# pulzn_regul_tor.net
KiCad netlist of a schematic drawn in EAGLE
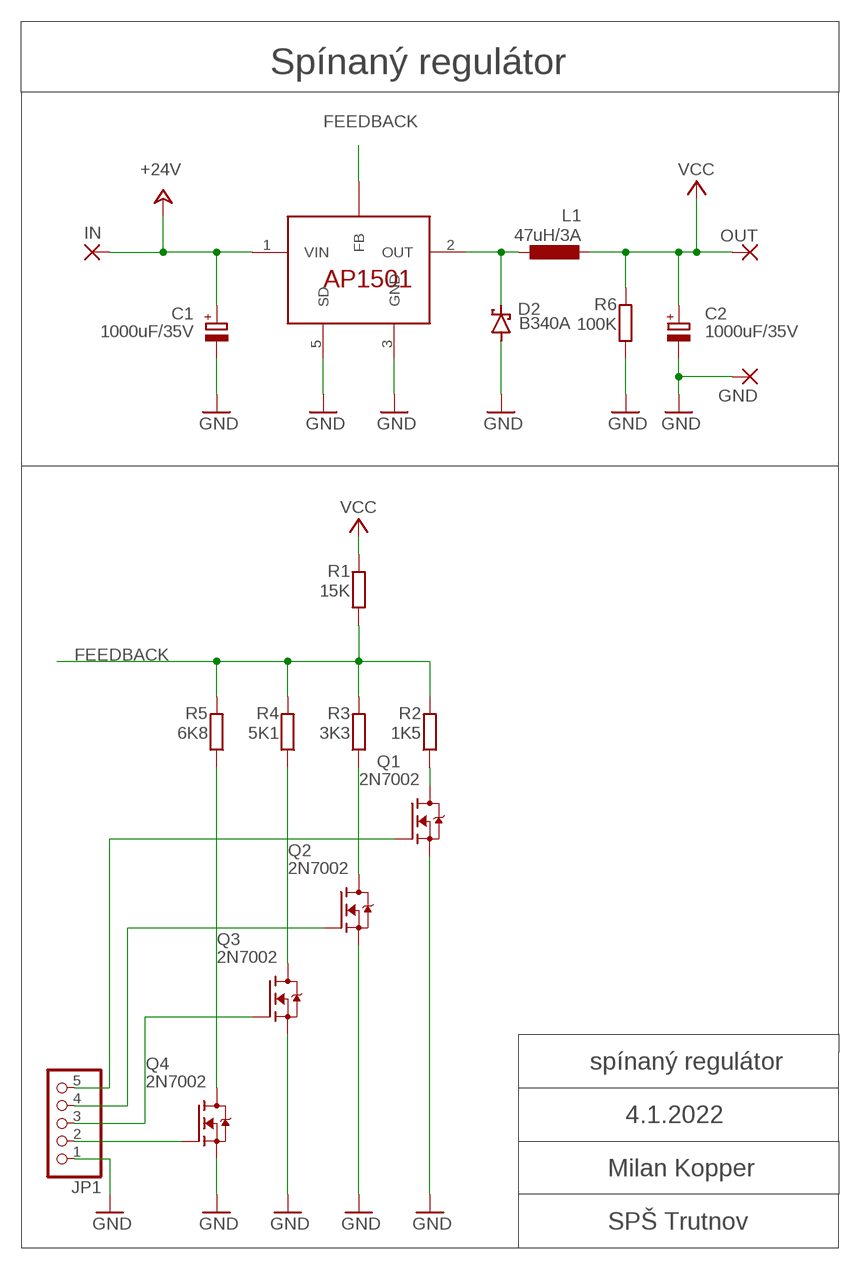
[diagram p0: schematic, sheet 1]

(export (version "E")
  (design (tool "Eeschema 10.0.6"))
  (components
    (comp (ref "C1")
      (value "1000uF/35V")
      (footprint "eagle-import:E5-10,5")
      (libsource (lib "eagle-import") (part "CPOL-EUE5-10.5"))
    )
    (comp (ref "C2")
      (value "1000uF/35V")
      (footprint "eagle-import:E5-10,5")
      (libsource (lib "eagle-import") (part "CPOL-EUE5-10.5"))
    )
    (comp (ref "D2")
      (value "B340A")
      (footprint "eagle-import:SMB")
      (libsource (lib "eagle-import") (part "MBRS130LT3"))
    )
    (comp (ref "GND")
      (value "3,17/1,3")
      (footprint "eagle-import:3,17_1,3")
      (libsource (lib "eagle-import") (part "3,17/1,3"))
    )
    (comp (ref "IN")
      (value "3,17/1,3")
      (footprint "eagle-import:3,17_1,3")
      (libsource (lib "eagle-import") (part "3,17/1,3"))
    )
    (comp (ref "JP1")
      (value "PINHD-1X5")
      (footprint "eagle-import:1X05")
      (libsource (lib "eagle-import") (part "PINHD-1X5"))
    )
    (comp (ref "L1")
      (value "47uH/3A")
      (footprint "eagle-import:DTMSS-16_0,033_6,0")
      (libsource (lib "eagle-import") (part "DTMSSDTMSS-16/0,033/6,0"))
    )
    (comp (ref "OUT")
      (value "3,17/1,3")
      (footprint "eagle-import:3,17_1,3")
      (libsource (lib "eagle-import") (part "3,17/1,3"))
    )
    (comp (ref "Q1")
      (value "2N7002")
      (footprint "eagle-import:SOT95P240X110-3N")
      (libsource (lib "eagle-import") (part "NX3008"))
    )
    (comp (ref "Q2")
      (value "2N7002")
      (footprint "eagle-import:SOT95P240X110-3N")
      (libsource (lib "eagle-import") (part "NX3008"))
    )
    (comp (ref "Q3")
      (value "2N7002")
      (footprint "eagle-import:SOT95P240X110-3N")
      (libsource (lib "eagle-import") (part "NX3008"))
    )
    (comp (ref "Q4")
      (value "2N7002")
      (footprint "eagle-import:SOT95P240X110-3N")
      (libsource (lib "eagle-import") (part "NX3008"))
    )
    (comp (ref "R1")
      (value "15K")
      (footprint "eagle-import:R0805")
      (libsource (lib "eagle-import") (part "R-EU_R0805"))
    )
    (comp (ref "R2")
      (value "1K5")
      (footprint "eagle-import:R0805")
      (libsource (lib "eagle-import") (part "R-EU_R0805"))
    )
    (comp (ref "R3")
      (value "3K3")
      (footprint "eagle-import:R0805")
      (libsource (lib "eagle-import") (part "R-EU_R0805"))
    )
    (comp (ref "R4")
      (value "5K1")
      (footprint "eagle-import:R0805")
      (libsource (lib "eagle-import") (part "R-EU_R0805"))
    )
    (comp (ref "R5")
      (value "6K8")
      (footprint "eagle-import:R0805")
      (libsource (lib "eagle-import") (part "R-EU_R0805"))
    )
    (comp (ref "R6")
      (value "100K")
      (footprint "eagle-import:R0805")
      (libsource (lib "eagle-import") (part "R-EU_R0805"))
    )
    (comp (ref "U$2")
      (value "AP1501TO220")
      (footprint "eagle-import:TO220-5")
      (libsource (lib "eagle-import") (part "AP1501TO220"))
    )
  )
  (nets
    (net (code "1") (name "+24V") (class "Default")
      (node (ref "C1") (pin "+") (pinfunction "+_+") (pintype "passive"))
      (node (ref "IN") (pin "1") (pinfunction "P_1") (pintype "passive"))
      (node (ref "U$2") (pin "1") (pinfunction "VIN_1") (pintype "bidirectional"))
    )
    (net (code "2") (name "/FEEDBACK") (class "Default")
      (node (ref "R1") (pin "1") (pinfunction "1_1") (pintype "passive"))
      (node (ref "R2") (pin "2") (pinfunction "2_2") (pintype "passive"))
      (node (ref "R3") (pin "2") (pinfunction "2_2") (pintype "passive"))
      (node (ref "R4") (pin "2") (pinfunction "2_2") (pintype "passive"))
      (node (ref "R5") (pin "2") (pinfunction "2_2") (pintype "passive"))
      (node (ref "U$2") (pin "4") (pinfunction "FB_4") (pintype "bidirectional"))
    )
    (net (code "3") (name "GND") (class "Default")
      (node (ref "C1") (pin "-") (pinfunction "-_-") (pintype "passive"))
      (node (ref "C2") (pin "-") (pinfunction "-_-") (pintype "passive"))
      (node (ref "D2") (pin "A") (pinfunction "A_A") (pintype "passive"))
      (node (ref "GND") (pin "1") (pinfunction "P_1") (pintype "passive"))
      (node (ref "JP1") (pin "1") (pinfunction "1_1") (pintype "passive"))
      (node (ref "Q1") (pin "2") (pinfunction "S_2") (pintype "passive"))
      (node (ref "Q2") (pin "2") (pinfunction "S_2") (pintype "passive"))
      (node (ref "Q3") (pin "2") (pinfunction "S_2") (pintype "passive"))
      (node (ref "Q4") (pin "2") (pinfunction "S_2") (pintype "passive"))
      (node (ref "R6") (pin "1") (pinfunction "1_1") (pintype "passive"))
      (node (ref "U$2") (pin "3") (pinfunction "GND_3") (pintype "bidirectional"))
      (node (ref "U$2") (pin "5") (pinfunction "SD_5") (pintype "bidirectional"))
    )
    (net (code "4") (name "Net-(L1-1)") (class "Default")
      (node (ref "D2") (pin "C") (pinfunction "C_C") (pintype "passive"))
      (node (ref "L1") (pin "P$1") (pinfunction "1_P$1") (pintype "passive"))
      (node (ref "U$2") (pin "2") (pinfunction "OUT_2") (pintype "bidirectional"))
    )
    (net (code "5") (name "Net-(Q1-D)") (class "Default")
      (node (ref "Q1") (pin "3") (pinfunction "D_3") (pintype "passive"))
      (node (ref "R2") (pin "1") (pinfunction "1_1") (pintype "passive"))
    )
    (net (code "6") (name "Net-(Q1-G)") (class "Default")
      (node (ref "JP1") (pin "5") (pinfunction "5_5") (pintype "passive"))
      (node (ref "Q1") (pin "1") (pinfunction "G_1") (pintype "passive"))
    )
    (net (code "7") (name "Net-(Q2-D)") (class "Default")
      (node (ref "Q2") (pin "3") (pinfunction "D_3") (pintype "passive"))
      (node (ref "R3") (pin "1") (pinfunction "1_1") (pintype "passive"))
    )
    (net (code "8") (name "Net-(Q2-G)") (class "Default")
      (node (ref "JP1") (pin "4") (pinfunction "4_4") (pintype "passive"))
      (node (ref "Q2") (pin "1") (pinfunction "G_1") (pintype "passive"))
    )
    (net (code "9") (name "Net-(Q3-D)") (class "Default")
      (node (ref "Q3") (pin "3") (pinfunction "D_3") (pintype "passive"))
      (node (ref "R4") (pin "1") (pinfunction "1_1") (pintype "passive"))
    )
    (net (code "10") (name "Net-(Q3-G)") (class "Default")
      (node (ref "JP1") (pin "3") (pinfunction "3_3") (pintype "passive"))
      (node (ref "Q3") (pin "1") (pinfunction "G_1") (pintype "passive"))
    )
    (net (code "11") (name "Net-(Q4-D)") (class "Default")
      (node (ref "Q4") (pin "3") (pinfunction "D_3") (pintype "passive"))
      (node (ref "R5") (pin "1") (pinfunction "1_1") (pintype "passive"))
    )
    (net (code "12") (name "Net-(Q4-G)") (class "Default")
      (node (ref "JP1") (pin "2") (pinfunction "2_2") (pintype "passive"))
      (node (ref "Q4") (pin "1") (pinfunction "G_1") (pintype "passive"))
    )
    (net (code "13") (name "VCC") (class "Default")
      (node (ref "C2") (pin "+") (pinfunction "+_+") (pintype "passive"))
      (node (ref "L1") (pin "P$2") (pinfunction "2_P$2") (pintype "passive"))
      (node (ref "OUT") (pin "1") (pinfunction "P_1") (pintype "passive"))
      (node (ref "R1") (pin "2") (pinfunction "2_2") (pintype "passive"))
      (node (ref "R6") (pin "2") (pinfunction "2_2") (pintype "passive"))
    )
  )
)
